# untitled.net
KiCad netlist of a schematic drawn in EAGLE
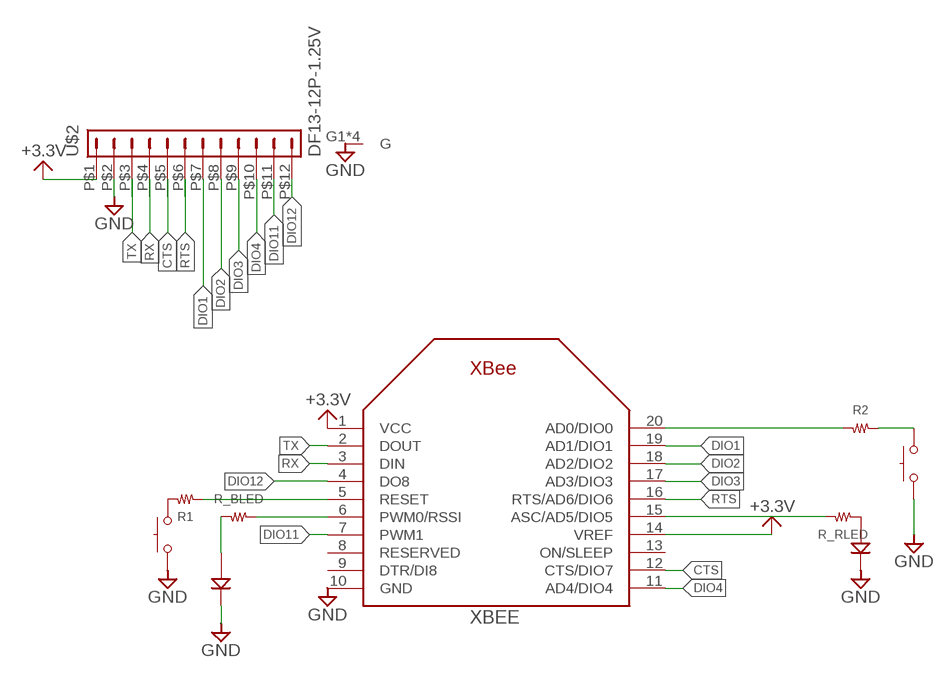
[diagram p0: schematic, sheet 1]

(export (version "E")
  (design (tool "Eeschema 10.0.6"))
  (components
    (comp (ref "COMM")
      (value "SKRPACE010")
      (footprint "eagle-import:SKRP")
      (libsource (lib "eagle-import") (part "SKRPACE010"))
    )
    (comp (ref "LED_B")
      (value "1608")
      (footprint "eagle-import:1608")
      (libsource (lib "eagle-import") (part "1608"))
    )
    (comp (ref "LED_R")
      (value "1608")
      (footprint "eagle-import:1608")
      (libsource (lib "eagle-import") (part "1608"))
    )
    (comp (ref "R1")
      (value "RESISTOR__SMD")
      (footprint "eagle-import:1608")
      (libsource (lib "eagle-import") (part "RESISTOR__SMD"))
    )
    (comp (ref "R2")
      (value "RESISTOR__SMD")
      (footprint "eagle-import:1608")
      (libsource (lib "eagle-import") (part "RESISTOR__SMD"))
    )
    (comp (ref "RESET")
      (value "SKRPACE010")
      (footprint "eagle-import:SKRP")
      (libsource (lib "eagle-import") (part "SKRPACE010"))
    )
    (comp (ref "R_BLED")
      (value "RESISTOR__SMD")
      (footprint "eagle-import:1608")
      (libsource (lib "eagle-import") (part "RESISTOR__SMD"))
    )
    (comp (ref "R_RLED")
      (value "RESISTOR__SMD")
      (footprint "eagle-import:1608")
      (libsource (lib "eagle-import") (part "RESISTOR__SMD"))
    )
    (comp (ref "U$2")
      (value "DF13-12P-1.25V")
      (footprint "eagle-import:DF13C-12P-1.25V")
      (libsource (lib "eagle-import") (part "DF13-12P-1.25V"))
    )
    (comp (ref "XBEE")
      (value "XBEE")
      (footprint "eagle-import:XBEE")
      (libsource (lib "eagle-import") (part "XBEE"))
    )
  )
  (nets
    (net (code "1") (name "+3.3V") (class "Default")
      (node (ref "U$2") (pin "P$1") (pinfunction "1_P$1") (pintype "passive"))
      (node (ref "XBEE") (pin "1") (pinfunction "VCC_1") (pintype "power_in"))
      (node (ref "XBEE") (pin "14") (pinfunction "VREF_14") (pintype "input"))
    )
    (net (code "2") (name "CTS") (class "Default")
      (node (ref "U$2") (pin "P$5") (pinfunction "5_P$5") (pintype "passive"))
      (node (ref "XBEE") (pin "12") (pinfunction "CTS/DIO7_12") (pintype "bidirectional"))
    )
    (net (code "3") (name "DIO1") (class "Default")
      (node (ref "U$2") (pin "P$7") (pinfunction "7_P$7") (pintype "passive"))
      (node (ref "XBEE") (pin "19") (pinfunction "AD1/DIO1_19") (pintype "bidirectional"))
    )
    (net (code "4") (name "DIO2") (class "Default")
      (node (ref "U$2") (pin "P$8") (pinfunction "8_P$8") (pintype "passive"))
      (node (ref "XBEE") (pin "18") (pinfunction "AD2/DIO2_18") (pintype "bidirectional"))
    )
    (net (code "5") (name "DIO3") (class "Default")
      (node (ref "U$2") (pin "P$9") (pinfunction "9_P$9") (pintype "passive"))
      (node (ref "XBEE") (pin "17") (pinfunction "AD3/DIO3_17") (pintype "bidirectional"))
    )
    (net (code "6") (name "DIO4") (class "Default")
      (node (ref "U$2") (pin "P$10") (pinfunction "10_P$10") (pintype "passive"))
      (node (ref "XBEE") (pin "11") (pinfunction "AD4/DIO4_11") (pintype "bidirectional"))
    )
    (net (code "7") (name "DIO11") (class "Default")
      (node (ref "U$2") (pin "P$11") (pinfunction "11_P$11") (pintype "passive"))
      (node (ref "XBEE") (pin "7") (pinfunction "PWM1_7") (pintype "output"))
    )
    (net (code "8") (name "DIO12") (class "Default")
      (node (ref "U$2") (pin "P$12") (pinfunction "12_P$12") (pintype "passive"))
      (node (ref "XBEE") (pin "4") (pinfunction "DO8_4") (pintype "output"))
    )
    (net (code "9") (name "GND") (class "Default")
      (node (ref "COMM") (pin "3") (pinfunction "P$2_3") (pintype "bidirectional"))
      (node (ref "COMM") (pin "4") (pinfunction "P$2_4") (pintype "bidirectional"))
      (node (ref "LED_B") (pin "2") (pinfunction "K_2") (pintype "bidirectional"))
      (node (ref "LED_R") (pin "2") (pinfunction "K_2") (pintype "bidirectional"))
      (node (ref "RESET") (pin "3") (pinfunction "P$2_3") (pintype "bidirectional"))
      (node (ref "RESET") (pin "4") (pinfunction "P$2_4") (pintype "bidirectional"))
      (node (ref "U$2") (pin "G1") (pinfunction "G_G1") (pintype "bidirectional"))
      (node (ref "U$2") (pin "G2") (pinfunction "G_G2") (pintype "bidirectional"))
      (node (ref "U$2") (pin "M$0") (pinfunction "G_M$0") (pintype "bidirectional"))
      (node (ref "U$2") (pin "M$1") (pinfunction "G_M$1") (pintype "bidirectional"))
      (node (ref "U$2") (pin "P$2") (pinfunction "2_P$2") (pintype "passive"))
      (node (ref "XBEE") (pin "10") (pinfunction "GND_10") (pintype "power_in"))
    )
    (net (code "10") (name "Net-(LED_B-A)") (class "Default")
      (node (ref "LED_B") (pin "1") (pinfunction "A_1") (pintype "bidirectional"))
      (node (ref "R_BLED") (pin "1") (pinfunction "P$1_1") (pintype "passive"))
    )
    (net (code "11") (name "Net-(LED_R-A)") (class "Default")
      (node (ref "LED_R") (pin "1") (pinfunction "A_1") (pintype "bidirectional"))
      (node (ref "R_RLED") (pin "1") (pinfunction "P$1_1") (pintype "passive"))
    )
    (net (code "12") (name "Net-(R1-P$1)") (class "Default")
      (node (ref "R1") (pin "1") (pinfunction "P$1_1") (pintype "passive"))
      (node (ref "XBEE") (pin "5") (pinfunction "RESET_5") (pintype "input"))
    )
    (net (code "13") (name "Net-(R1-P$2)") (class "Default")
      (node (ref "R1") (pin "2") (pinfunction "P$2_2") (pintype "passive"))
      (node (ref "RESET") (pin "1") (pinfunction "P$1_1") (pintype "bidirectional"))
      (node (ref "RESET") (pin "2") (pinfunction "P$1_2") (pintype "bidirectional"))
    )
    (net (code "14") (name "Net-(R2-P$1)") (class "Default")
      (node (ref "R2") (pin "1") (pinfunction "P$1_1") (pintype "passive"))
      (node (ref "XBEE") (pin "20") (pinfunction "AD0/DIO0_20") (pintype "bidirectional"))
    )
    (net (code "15") (name "Net-(R2-P$2)") (class "Default")
      (node (ref "COMM") (pin "1") (pinfunction "P$1_1") (pintype "bidirectional"))
      (node (ref "COMM") (pin "2") (pinfunction "P$1_2") (pintype "bidirectional"))
      (node (ref "R2") (pin "2") (pinfunction "P$2_2") (pintype "passive"))
    )
    (net (code "16") (name "Net-(R_BLED-P$2)") (class "Default")
      (node (ref "R_BLED") (pin "2") (pinfunction "P$2_2") (pintype "passive"))
      (node (ref "XBEE") (pin "6") (pinfunction "PWM0/RSSI_6") (pintype "output"))
    )
    (net (code "17") (name "Net-(R_RLED-P$2)") (class "Default")
      (node (ref "R_RLED") (pin "2") (pinfunction "P$2_2") (pintype "passive"))
      (node (ref "XBEE") (pin "15") (pinfunction "ASC/AD5/DIO5_15") (pintype "bidirectional"))
    )
    (net (code "18") (name "RTS") (class "Default")
      (node (ref "U$2") (pin "P$6") (pinfunction "6_P$6") (pintype "passive"))
      (node (ref "XBEE") (pin "16") (pinfunction "RTS/AD6/DIO6_16") (pintype "bidirectional"))
    )
    (net (code "19") (name "RX") (class "Default")
      (node (ref "U$2") (pin "P$4") (pinfunction "4_P$4") (pintype "passive"))
      (node (ref "XBEE") (pin "3") (pinfunction "DIN_3") (pintype "input"))
    )
    (net (code "20") (name "TX") (class "Default")
      (node (ref "U$2") (pin "P$3") (pinfunction "3_P$3") (pintype "passive"))
      (node (ref "XBEE") (pin "2") (pinfunction "DOUT_2") (pintype "output"))
    )
    (net (code "21") (name "unconnected-(XBEE-DTR{slash}DI8-Pad9)") (class "Default")
      (node (ref "XBEE") (pin "9") (pinfunction "DTR/DI8_9") (pintype "input"))
    )
    (net (code "22") (name "unconnected-(XBEE-ON{slash}SLEEP-Pad13)") (class "Default")
      (node (ref "XBEE") (pin "13") (pinfunction "ON/SLEEP_13") (pintype "output"))
    )
    (net (code "23") (name "unconnected-(XBEE-RESERVED-Pad8)") (class "Default")
      (node (ref "XBEE") (pin "8") (pinfunction "RESERVED_8") (pintype "no_connect"))
    )
  )
)
